# MTF0320CMIL-04.net
KiCad netlist of a schematic drawn in Altium Designer
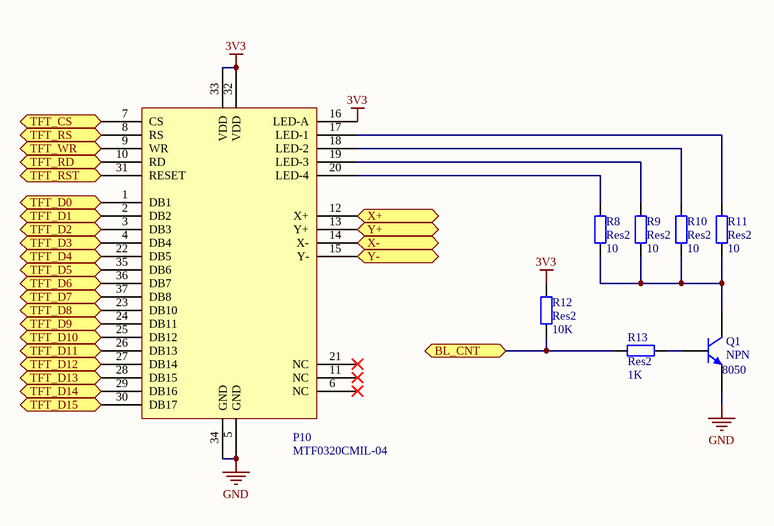
[diagram p0: MTF0320CMIL-04.SchDoc]

(export (version "E")
  (design (tool "Eeschema 10.0.6"))
  (components
    (comp (ref "P10")
      (value "MTF0320CMIL-04")
      (footprint "37 Pin 1mm pitch FPC")
      (description "3.2\" TFT LCD module with touch panel")
      (libsource (lib "BrewBit") (part "MTF0320CMIL-04"))
    )
    (comp (ref "Q1")
      (value "NPN")
      (footprint "SOT23_M")
      (description "NPN Bipolar Transistor")
      (fields (field (name "ALTIUM_VALUE") "8050"))
      (libsource (lib "Miscellaneous Devices") (part "NPN"))
    )
    (comp (ref "R8")
      (value "Res2")
      (footprint "0603")
      (description "Resistor")
      (fields (field (name "ALTIUM_VALUE") "10"))
      (libsource (lib "Miscellaneous Devices") (part "Res2"))
    )
    (comp (ref "R9")
      (value "Res2")
      (footprint "0603")
      (description "Resistor")
      (fields (field (name "ALTIUM_VALUE") "10"))
      (libsource (lib "Miscellaneous Devices") (part "Res2"))
    )
    (comp (ref "R10")
      (value "Res2")
      (footprint "0603")
      (description "Resistor")
      (fields (field (name "ALTIUM_VALUE") "10"))
      (libsource (lib "Miscellaneous Devices") (part "Res2"))
    )
    (comp (ref "R11")
      (value "Res2")
      (footprint "0603")
      (description "Resistor")
      (fields (field (name "ALTIUM_VALUE") "10"))
      (libsource (lib "Miscellaneous Devices") (part "Res2"))
    )
    (comp (ref "R12")
      (value "Res2")
      (footprint "0603")
      (description "Resistor")
      (fields (field (name "ALTIUM_VALUE") "10K"))
      (libsource (lib "Miscellaneous Devices") (part "Res2"))
    )
    (comp (ref "R13")
      (value "Res2")
      (footprint "0603")
      (description "Resistor")
      (fields (field (name "ALTIUM_VALUE") "1K"))
      (libsource (lib "") (part "Res2_1"))
    )
  )
  (nets
    (net (code "1") (name "/BL_CNT") (class "Default")
      (node (ref "R12") (pin "1") (pinfunction "1_1") (pintype "passive"))
      (node (ref "R13") (pin "2") (pinfunction "2_2") (pintype "passive"))
    )
    (net (code "2") (name "/TFT_CS") (class "Default")
      (node (ref "P10") (pin "7") (pinfunction "CS_7") (pintype "passive"))
    )
    (net (code "3") (name "/TFT_D0") (class "Default")
      (node (ref "P10") (pin "1") (pinfunction "DB1_1") (pintype "passive"))
    )
    (net (code "4") (name "/TFT_D1") (class "Default")
      (node (ref "P10") (pin "2") (pinfunction "DB2_2") (pintype "passive"))
    )
    (net (code "5") (name "/TFT_D2") (class "Default")
      (node (ref "P10") (pin "3") (pinfunction "DB3_3") (pintype "passive"))
    )
    (net (code "6") (name "/TFT_D3") (class "Default")
      (node (ref "P10") (pin "4") (pinfunction "DB4_4") (pintype "passive"))
    )
    (net (code "7") (name "/TFT_D4") (class "Default")
      (node (ref "P10") (pin "22") (pinfunction "DB5_22") (pintype "passive"))
    )
    (net (code "8") (name "/TFT_D5") (class "Default")
      (node (ref "P10") (pin "35") (pinfunction "DB6_35") (pintype "passive"))
    )
    (net (code "9") (name "/TFT_D6") (class "Default")
      (node (ref "P10") (pin "36") (pinfunction "DB7_36") (pintype "passive"))
    )
    (net (code "10") (name "/TFT_D7") (class "Default")
      (node (ref "P10") (pin "37") (pinfunction "DB8_37") (pintype "passive"))
    )
    (net (code "11") (name "/TFT_D8") (class "Default")
      (node (ref "P10") (pin "23") (pinfunction "DB10_23") (pintype "passive"))
    )
    (net (code "12") (name "/TFT_D9") (class "Default")
      (node (ref "P10") (pin "24") (pinfunction "DB11_24") (pintype "passive"))
    )
    (net (code "13") (name "/TFT_D10") (class "Default")
      (node (ref "P10") (pin "25") (pinfunction "DB12_25") (pintype "passive"))
    )
    (net (code "14") (name "/TFT_D11") (class "Default")
      (node (ref "P10") (pin "26") (pinfunction "DB13_26") (pintype "passive"))
    )
    (net (code "15") (name "/TFT_D12") (class "Default")
      (node (ref "P10") (pin "27") (pinfunction "DB14_27") (pintype "passive"))
    )
    (net (code "16") (name "/TFT_D13") (class "Default")
      (node (ref "P10") (pin "28") (pinfunction "DB15_28") (pintype "passive"))
    )
    (net (code "17") (name "/TFT_D14") (class "Default")
      (node (ref "P10") (pin "29") (pinfunction "DB16_29") (pintype "passive"))
    )
    (net (code "18") (name "/TFT_D15") (class "Default")
      (node (ref "P10") (pin "30") (pinfunction "DB17_30") (pintype "passive"))
    )
    (net (code "19") (name "/TFT_RD") (class "Default")
      (node (ref "P10") (pin "10") (pinfunction "RD_10") (pintype "passive"))
    )
    (net (code "20") (name "/TFT_RS") (class "Default")
      (node (ref "P10") (pin "8") (pinfunction "RS_8") (pintype "passive"))
    )
    (net (code "21") (name "/TFT_RST") (class "Default")
      (node (ref "P10") (pin "31") (pinfunction "RESET_31") (pintype "passive"))
    )
    (net (code "22") (name "/TFT_WR") (class "Default")
      (node (ref "P10") (pin "9") (pinfunction "WR_9") (pintype "passive"))
    )
    (net (code "23") (name "/X+") (class "Default")
      (node (ref "P10") (pin "12") (pinfunction "X+_12") (pintype "passive"))
    )
    (net (code "24") (name "/X-") (class "Default")
      (node (ref "P10") (pin "14") (pinfunction "X-_14") (pintype "passive"))
    )
    (net (code "25") (name "/Y+") (class "Default")
      (node (ref "P10") (pin "13") (pinfunction "Y+_13") (pintype "passive"))
    )
    (net (code "26") (name "/Y-") (class "Default")
      (node (ref "P10") (pin "15") (pinfunction "Y-_15") (pintype "passive"))
    )
    (net (code "27") (name "3V3") (class "Default")
      (node (ref "P10") (pin "16") (pinfunction "LED-A_16") (pintype "passive"))
      (node (ref "P10") (pin "32") (pinfunction "VDD_32") (pintype "passive"))
      (node (ref "P10") (pin "33") (pinfunction "VDD_33") (pintype "passive"))
      (node (ref "R12") (pin "2") (pinfunction "2_2") (pintype "passive"))
    )
    (net (code "28") (name "GND") (class "Default")
      (node (ref "P10") (pin "34") (pinfunction "GND_34") (pintype "passive"))
      (node (ref "P10") (pin "5") (pinfunction "GND_5") (pintype "passive"))
      (node (ref "Q1") (pin "3") (pinfunction "E_3") (pintype "passive"))
    )
    (net (code "29") (name "Net-(P10-LED-1)") (class "Default")
      (node (ref "P10") (pin "17") (pinfunction "LED-1_17") (pintype "passive"))
      (node (ref "R11") (pin "2") (pinfunction "2_2") (pintype "passive"))
    )
    (net (code "30") (name "Net-(P10-LED-2)") (class "Default")
      (node (ref "P10") (pin "18") (pinfunction "LED-2_18") (pintype "passive"))
      (node (ref "R10") (pin "2") (pinfunction "2_2") (pintype "passive"))
    )
    (net (code "31") (name "Net-(P10-LED-3)") (class "Default")
      (node (ref "P10") (pin "19") (pinfunction "LED-3_19") (pintype "passive"))
      (node (ref "R9") (pin "2") (pinfunction "2_2") (pintype "passive"))
    )
    (net (code "32") (name "Net-(P10-LED-4)") (class "Default")
      (node (ref "P10") (pin "20") (pinfunction "LED-4_20") (pintype "passive"))
      (node (ref "R8") (pin "2") (pinfunction "2_2") (pintype "passive"))
    )
    (net (code "33") (name "Net-(Q1-B)") (class "Default")
      (node (ref "Q1") (pin "2") (pinfunction "B_2") (pintype "passive"))
      (node (ref "R13") (pin "1") (pinfunction "1_1") (pintype "passive"))
    )
    (net (code "34") (name "Net-(Q1-C)") (class "Default")
      (node (ref "Q1") (pin "1") (pinfunction "C_1") (pintype "passive"))
      (node (ref "R10") (pin "1") (pinfunction "1_1") (pintype "passive"))
      (node (ref "R11") (pin "1") (pinfunction "1_1") (pintype "passive"))
      (node (ref "R8") (pin "1") (pinfunction "1_1") (pintype "passive"))
      (node (ref "R9") (pin "1") (pinfunction "1_1") (pintype "passive"))
    )
    (net (code "35") (name "unconnected-(P10-NC-Pad6)") (class "Default")
      (node (ref "P10") (pin "6") (pinfunction "NC_6") (pintype "passive+no_connect"))
    )
    (net (code "36") (name "unconnected-(P10-NC-Pad11)") (class "Default")
      (node (ref "P10") (pin "11") (pinfunction "NC_11") (pintype "passive+no_connect"))
    )
    (net (code "37") (name "unconnected-(P10-NC-Pad21)") (class "Default")
      (node (ref "P10") (pin "21") (pinfunction "NC_21") (pintype "passive+no_connect"))
    )
  )
)
